# ProPrj_USB_Hub_Port_PCB_2026-05-02.net
KiCad netlist of a schematic drawn in EasyEDA Pro
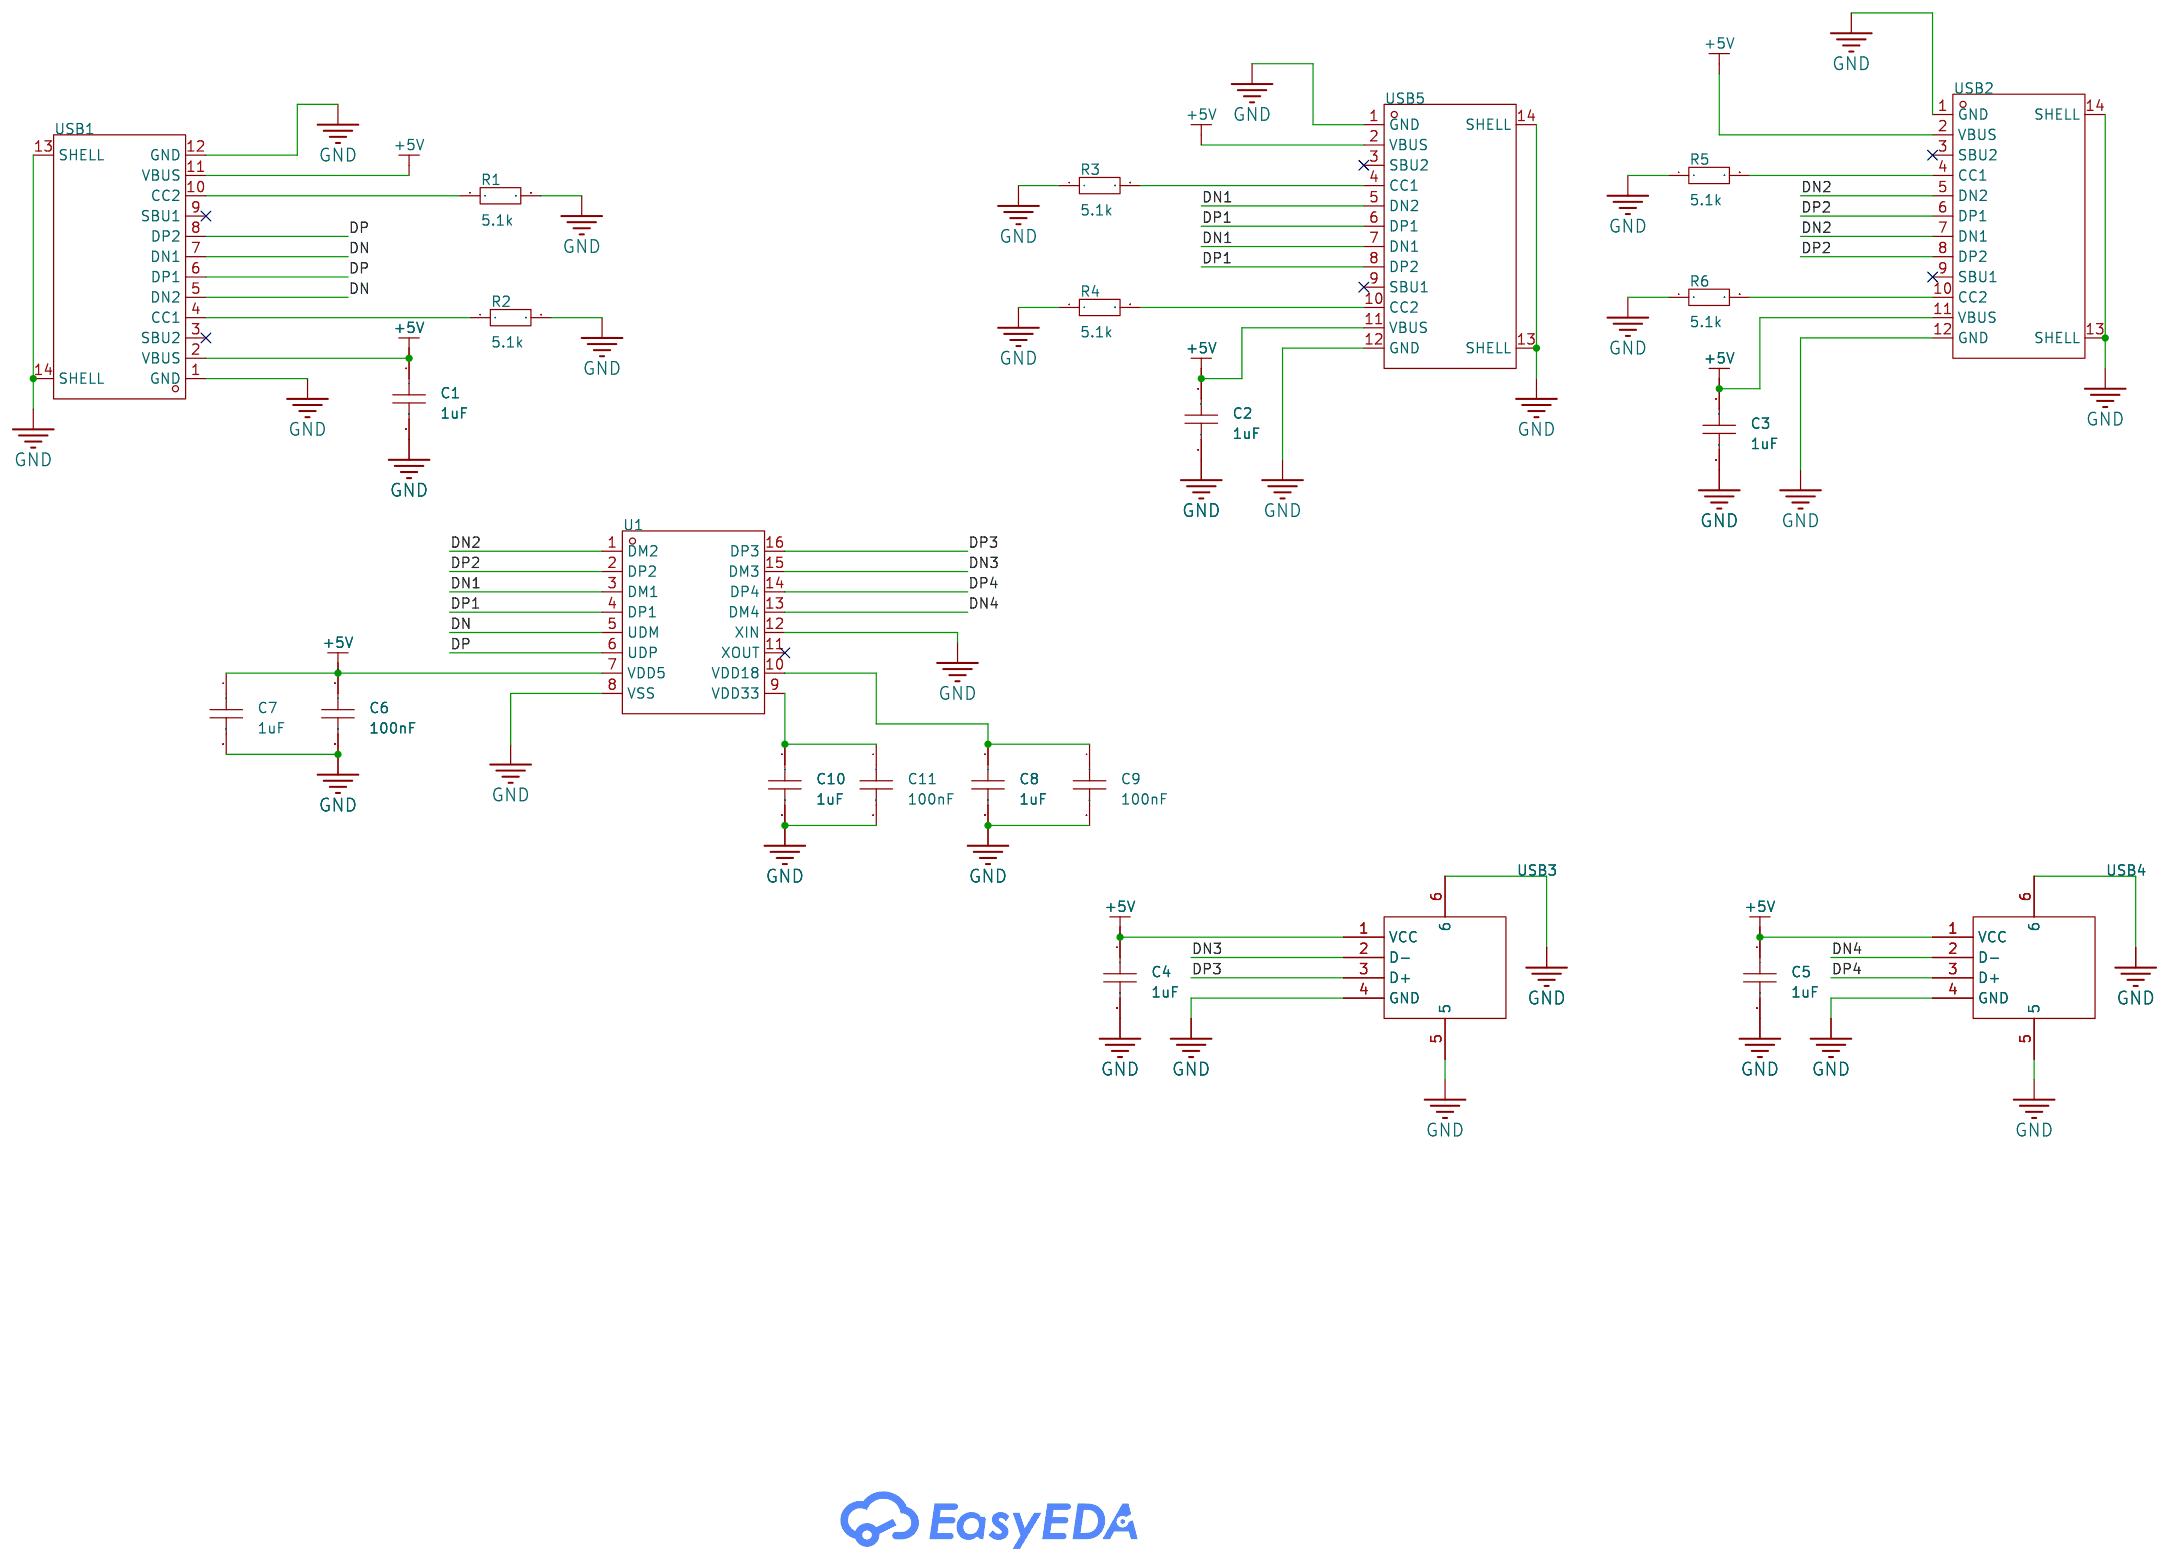
[diagram p0: schematic sheet]

(export (version "E")
  (design (tool "Eeschema 10.0.6"))
  (components
    (comp (ref "C1") (value "1uF") (footprint "easyedapro:C0603") (libsource (lib "easyedapro") (part "CAP")))
    (comp (ref "C2") (value "1uF") (footprint "easyedapro:C0603") (libsource (lib "easyedapro") (part "CAP")))
    (comp (ref "C3") (value "1uF") (footprint "easyedapro:C0603") (libsource (lib "easyedapro") (part "CAP")))
    (comp (ref "C4") (value "1uF") (footprint "easyedapro:C0603") (libsource (lib "easyedapro") (part "CAP")))
    (comp (ref "C5") (value "1uF") (footprint "easyedapro:C0603") (libsource (lib "easyedapro") (part "CAP")))
    (comp (ref "C6")
      (value "100nF")
      (footprint "easyedapro:C0603")
      (libsource (lib "easyedapro") (part "CAP"))
    )
    (comp (ref "C7") (value "1uF") (footprint "easyedapro:C0603") (libsource (lib "easyedapro") (part "CAP")))
    (comp (ref "C8") (value "1uF") (footprint "easyedapro:C0603") (libsource (lib "easyedapro") (part "CAP")))
    (comp (ref "C9")
      (value "100nF")
      (footprint "easyedapro:C0603")
      (libsource (lib "easyedapro") (part "CAP"))
    )
    (comp (ref "C10")
      (value "1uF")
      (footprint "easyedapro:C0603")
      (libsource (lib "easyedapro") (part "CAP"))
    )
    (comp (ref "C11")
      (value "100nF")
      (footprint "easyedapro:C0603")
      (libsource (lib "easyedapro") (part "CAP"))
    )
    (comp (ref "R1")
      (value "5.1k")
      (footprint "easyedapro:R0603")
      (libsource (lib "easyedapro") (part "Res"))
    )
    (comp (ref "R2")
      (value "5.1k")
      (footprint "easyedapro:R0603")
      (libsource (lib "easyedapro") (part "Res"))
    )
    (comp (ref "R3")
      (value "5.1k")
      (footprint "easyedapro:R0603")
      (libsource (lib "easyedapro") (part "Res"))
    )
    (comp (ref "R4")
      (value "5.1k")
      (footprint "easyedapro:R0603")
      (libsource (lib "easyedapro") (part "Res"))
    )
    (comp (ref "R5")
      (value "5.1k")
      (footprint "easyedapro:R0603")
      (libsource (lib "easyedapro") (part "Res"))
    )
    (comp (ref "R6")
      (value "5.1k")
      (footprint "easyedapro:R0603")
      (libsource (lib "easyedapro") (part "Res"))
    )
    (comp (ref "U1")
      (value "SL2.1s")
      (footprint "easyedapro:SSOP-16_L4.6-W2.6-P0.53-LS4.0-BL")
      (fields (field (name "Manufacturer") "CoreChips(和芯润德)"))
      (libsource (lib "easyedapro") (part "SL2.1S"))
    )
    (comp (ref "USB1")
      (value "TYPE-C 16PIN 2MD(073)")
      (footprint "easyedapro:USB-C-SMD_TYPE-C-6PIN-2MD-073")
      (fields (field (name "Manufacturer") "SHOU HAN(首韩)"))
      (libsource (lib "easyedapro") (part "TYPE-C 16PIN 2MD(073)"))
    )
    (comp (ref "USB2")
      (value "TYPE-C 16PIN 2MD(073)")
      (footprint "easyedapro:USB-C-SMD_TYPE-C-6PIN-2MD-073")
      (fields (field (name "Manufacturer") "SHOU HAN(首韩)"))
      (libsource (lib "easyedapro") (part "TYPE-C 16PIN 2MD(073)"))
    )
    (comp (ref "USB3")
      (value "10.0 QHHTZB6.3")
      (footprint "easyedapro:USB-A-TH_10.0QHHTZB6.3")
      (fields (field (name "Manufacturer") "SHOU HAN(首韩)"))
      (libsource (lib "easyedapro") (part "10.0 QHHTZB6.3"))
    )
    (comp (ref "USB4")
      (value "10.0 QHHTZB6.3")
      (footprint "easyedapro:USB-A-TH_10.0QHHTZB6.3")
      (fields (field (name "Manufacturer") "SHOU HAN(首韩)"))
      (libsource (lib "easyedapro") (part "10.0 QHHTZB6.3"))
    )
    (comp (ref "USB5")
      (value "TYPE-C 16PIN 2MD(073)")
      (footprint "easyedapro:USB-C-SMD_TYPE-C-6PIN-2MD-073")
      (fields (field (name "Manufacturer") "SHOU HAN(首韩)"))
      (libsource (lib "easyedapro") (part "TYPE-C 16PIN 2MD(073)"))
    )
  )
  (nets
    (net (code "1") (name "+5V") (class "Default")
      (node (ref "C1") (pin "1") (pinfunction "1_1") (pintype "input"))
      (node (ref "C2") (pin "1") (pinfunction "1_1") (pintype "input"))
      (node (ref "C3") (pin "1") (pinfunction "1_1") (pintype "input"))
      (node (ref "C4") (pin "1") (pinfunction "1_1") (pintype "input"))
      (node (ref "C5") (pin "1") (pinfunction "1_1") (pintype "input"))
      (node (ref "C6") (pin "1") (pinfunction "1_1") (pintype "input"))
      (node (ref "C7") (pin "1") (pinfunction "1_1") (pintype "input"))
      (node (ref "U1") (pin "7") (pinfunction "VDD5_7") (pintype "unspecified"))
      (node (ref "USB1") (pin "11") (pinfunction "VBUS_11") (pintype "unspecified"))
      (node (ref "USB1") (pin "2") (pinfunction "VBUS_2") (pintype "unspecified"))
      (node (ref "USB2") (pin "11") (pinfunction "VBUS_11") (pintype "unspecified"))
      (node (ref "USB2") (pin "2") (pinfunction "VBUS_2") (pintype "unspecified"))
      (node (ref "USB3") (pin "1") (pinfunction "VCC_1") (pintype "unspecified"))
      (node (ref "USB4") (pin "1") (pinfunction "VCC_1") (pintype "unspecified"))
      (node (ref "USB5") (pin "11") (pinfunction "VBUS_11") (pintype "unspecified"))
      (node (ref "USB5") (pin "2") (pinfunction "VBUS_2") (pintype "unspecified"))
    )
    (net (code "2") (name "/DN") (class "Default")
      (node (ref "U1") (pin "5") (pinfunction "UDM_5") (pintype "unspecified"))
      (node (ref "USB1") (pin "5") (pinfunction "DN2_5") (pintype "unspecified"))
      (node (ref "USB1") (pin "7") (pinfunction "DN1_7") (pintype "unspecified"))
    )
    (net (code "3") (name "/DN1") (class "Default")
      (node (ref "U1") (pin "3") (pinfunction "DM1_3") (pintype "unspecified"))
      (node (ref "USB5") (pin "5") (pinfunction "DN2_5") (pintype "unspecified"))
      (node (ref "USB5") (pin "7") (pinfunction "DN1_7") (pintype "unspecified"))
    )
    (net (code "4") (name "/DN2") (class "Default")
      (node (ref "U1") (pin "1") (pinfunction "DM2_1") (pintype "unspecified"))
      (node (ref "USB2") (pin "5") (pinfunction "DN2_5") (pintype "unspecified"))
      (node (ref "USB2") (pin "7") (pinfunction "DN1_7") (pintype "unspecified"))
    )
    (net (code "5") (name "/DN3") (class "Default")
      (node (ref "U1") (pin "15") (pinfunction "DM3_15") (pintype "unspecified"))
      (node (ref "USB3") (pin "2") (pinfunction "D-_2") (pintype "unspecified"))
    )
    (net (code "6") (name "/DN4") (class "Default")
      (node (ref "U1") (pin "13") (pinfunction "DM4_13") (pintype "unspecified"))
      (node (ref "USB4") (pin "2") (pinfunction "D-_2") (pintype "unspecified"))
    )
    (net (code "7") (name "/DP") (class "Default")
      (node (ref "U1") (pin "6") (pinfunction "UDP_6") (pintype "unspecified"))
      (node (ref "USB1") (pin "6") (pinfunction "DP1_6") (pintype "unspecified"))
      (node (ref "USB1") (pin "8") (pinfunction "DP2_8") (pintype "unspecified"))
    )
    (net (code "8") (name "/DP1") (class "Default")
      (node (ref "U1") (pin "4") (pinfunction "DP1_4") (pintype "unspecified"))
      (node (ref "USB5") (pin "6") (pinfunction "DP1_6") (pintype "unspecified"))
      (node (ref "USB5") (pin "8") (pinfunction "DP2_8") (pintype "unspecified"))
    )
    (net (code "9") (name "/DP2") (class "Default")
      (node (ref "U1") (pin "2") (pinfunction "DP2_2") (pintype "unspecified"))
      (node (ref "USB2") (pin "6") (pinfunction "DP1_6") (pintype "unspecified"))
      (node (ref "USB2") (pin "8") (pinfunction "DP2_8") (pintype "unspecified"))
    )
    (net (code "10") (name "/DP3") (class "Default")
      (node (ref "U1") (pin "16") (pinfunction "DP3_16") (pintype "unspecified"))
      (node (ref "USB3") (pin "3") (pinfunction "D+_3") (pintype "unspecified"))
    )
    (net (code "11") (name "/DP4") (class "Default")
      (node (ref "U1") (pin "14") (pinfunction "DP4_14") (pintype "unspecified"))
      (node (ref "USB4") (pin "3") (pinfunction "D+_3") (pintype "unspecified"))
    )
    (net (code "12") (name "GND") (class "Default")
      (node (ref "C1") (pin "2") (pinfunction "2_2") (pintype "input"))
      (node (ref "C10") (pin "2") (pinfunction "2_2") (pintype "input"))
      (node (ref "C11") (pin "2") (pinfunction "2_2") (pintype "input"))
      (node (ref "C2") (pin "2") (pinfunction "2_2") (pintype "input"))
      (node (ref "C3") (pin "2") (pinfunction "2_2") (pintype "input"))
      (node (ref "C4") (pin "2") (pinfunction "2_2") (pintype "input"))
      (node (ref "C5") (pin "2") (pinfunction "2_2") (pintype "input"))
      (node (ref "C6") (pin "2") (pinfunction "2_2") (pintype "input"))
      (node (ref "C7") (pin "2") (pinfunction "2_2") (pintype "input"))
      (node (ref "C8") (pin "2") (pinfunction "2_2") (pintype "input"))
      (node (ref "C9") (pin "2") (pinfunction "2_2") (pintype "input"))
      (node (ref "R1") (pin "2") (pinfunction "2_2") (pintype "input"))
      (node (ref "R2") (pin "2") (pinfunction "2_2") (pintype "input"))
      (node (ref "R3") (pin "1") (pinfunction "1_1") (pintype "input"))
      (node (ref "R4") (pin "1") (pinfunction "1_1") (pintype "input"))
      (node (ref "R5") (pin "1") (pinfunction "1_1") (pintype "input"))
      (node (ref "R6") (pin "1") (pinfunction "1_1") (pintype "input"))
      (node (ref "U1") (pin "12") (pinfunction "XIN_12") (pintype "unspecified"))
      (node (ref "U1") (pin "8") (pinfunction "VSS_8") (pintype "unspecified"))
      (node (ref "USB1") (pin "1") (pinfunction "GND_1") (pintype "unspecified"))
      (node (ref "USB1") (pin "12") (pinfunction "GND_12") (pintype "unspecified"))
      (node (ref "USB1") (pin "13") (pinfunction "SHELL_13") (pintype "unspecified"))
      (node (ref "USB1") (pin "14") (pinfunction "SHELL_14") (pintype "unspecified"))
      (node (ref "USB2") (pin "1") (pinfunction "GND_1") (pintype "unspecified"))
      (node (ref "USB2") (pin "12") (pinfunction "GND_12") (pintype "unspecified"))
      (node (ref "USB2") (pin "13") (pinfunction "SHELL_13") (pintype "unspecified"))
      (node (ref "USB2") (pin "14") (pinfunction "SHELL_14") (pintype "unspecified"))
      (node (ref "USB3") (pin "4") (pinfunction "GND_4") (pintype "unspecified"))
      (node (ref "USB3") (pin "5") (pinfunction "5_5") (pintype "unspecified"))
      (node (ref "USB3") (pin "6") (pinfunction "6_6") (pintype "unspecified"))
      (node (ref "USB4") (pin "4") (pinfunction "GND_4") (pintype "unspecified"))
      (node (ref "USB4") (pin "5") (pinfunction "5_5") (pintype "unspecified"))
      (node (ref "USB4") (pin "6") (pinfunction "6_6") (pintype "unspecified"))
      (node (ref "USB5") (pin "1") (pinfunction "GND_1") (pintype "unspecified"))
      (node (ref "USB5") (pin "12") (pinfunction "GND_12") (pintype "unspecified"))
      (node (ref "USB5") (pin "13") (pinfunction "SHELL_13") (pintype "unspecified"))
      (node (ref "USB5") (pin "14") (pinfunction "SHELL_14") (pintype "unspecified"))
    )
    (net (code "13") (name "Net-(U1-VDD18)") (class "Default")
      (node (ref "C8") (pin "1") (pinfunction "1_1") (pintype "input"))
      (node (ref "C9") (pin "1") (pinfunction "1_1") (pintype "input"))
      (node (ref "U1") (pin "10") (pinfunction "VDD18_10") (pintype "unspecified"))
    )
    (net (code "14") (name "Net-(U1-VDD33)") (class "Default")
      (node (ref "C10") (pin "1") (pinfunction "1_1") (pintype "input"))
      (node (ref "C11") (pin "1") (pinfunction "1_1") (pintype "input"))
      (node (ref "U1") (pin "9") (pinfunction "VDD33_9") (pintype "unspecified"))
    )
    (net (code "15") (name "Net-(USB1-CC1)") (class "Default")
      (node (ref "R2") (pin "1") (pinfunction "1_1") (pintype "input"))
      (node (ref "USB1") (pin "4") (pinfunction "CC1_4") (pintype "unspecified"))
    )
    (net (code "16") (name "Net-(USB1-CC2)") (class "Default")
      (node (ref "R1") (pin "1") (pinfunction "1_1") (pintype "input"))
      (node (ref "USB1") (pin "10") (pinfunction "CC2_10") (pintype "unspecified"))
    )
    (net (code "17") (name "Net-(USB2-CC1)") (class "Default")
      (node (ref "R5") (pin "2") (pinfunction "2_2") (pintype "input"))
      (node (ref "USB2") (pin "4") (pinfunction "CC1_4") (pintype "unspecified"))
    )
    (net (code "18") (name "Net-(USB2-CC2)") (class "Default")
      (node (ref "R6") (pin "2") (pinfunction "2_2") (pintype "input"))
      (node (ref "USB2") (pin "10") (pinfunction "CC2_10") (pintype "unspecified"))
    )
    (net (code "19") (name "Net-(USB5-CC1)") (class "Default")
      (node (ref "R3") (pin "2") (pinfunction "2_2") (pintype "input"))
      (node (ref "USB5") (pin "4") (pinfunction "CC1_4") (pintype "unspecified"))
    )
    (net (code "20") (name "Net-(USB5-CC2)") (class "Default")
      (node (ref "R4") (pin "2") (pinfunction "2_2") (pintype "input"))
      (node (ref "USB5") (pin "10") (pinfunction "CC2_10") (pintype "unspecified"))
    )
    (net (code "21") (name "unconnected-(U1-XOUT-Pad11)") (class "Default")
      (node (ref "U1") (pin "11") (pinfunction "XOUT_11") (pintype "unspecified+no_connect"))
    )
    (net (code "22") (name "unconnected-(USB1-SBU1-Pad9)") (class "Default")
      (node (ref "USB1") (pin "9") (pinfunction "SBU1_9") (pintype "unspecified+no_connect"))
    )
    (net (code "23") (name "unconnected-(USB1-SBU2-Pad3)") (class "Default")
      (node (ref "USB1") (pin "3") (pinfunction "SBU2_3") (pintype "unspecified+no_connect"))
    )
    (net (code "24") (name "unconnected-(USB2-SBU1-Pad9)") (class "Default")
      (node (ref "USB2") (pin "9") (pinfunction "SBU1_9") (pintype "unspecified+no_connect"))
    )
    (net (code "25") (name "unconnected-(USB2-SBU2-Pad3)") (class "Default")
      (node (ref "USB2") (pin "3") (pinfunction "SBU2_3") (pintype "unspecified+no_connect"))
    )
    (net (code "26") (name "unconnected-(USB5-SBU1-Pad9)") (class "Default")
      (node (ref "USB5") (pin "9") (pinfunction "SBU1_9") (pintype "unspecified+no_connect"))
    )
    (net (code "27") (name "unconnected-(USB5-SBU2-Pad3)") (class "Default")
      (node (ref "USB5") (pin "3") (pinfunction "SBU2_3") (pintype "unspecified+no_connect"))
    )
  )
)
